# MCU.net
KiCad netlist of a schematic drawn in Altium Designer
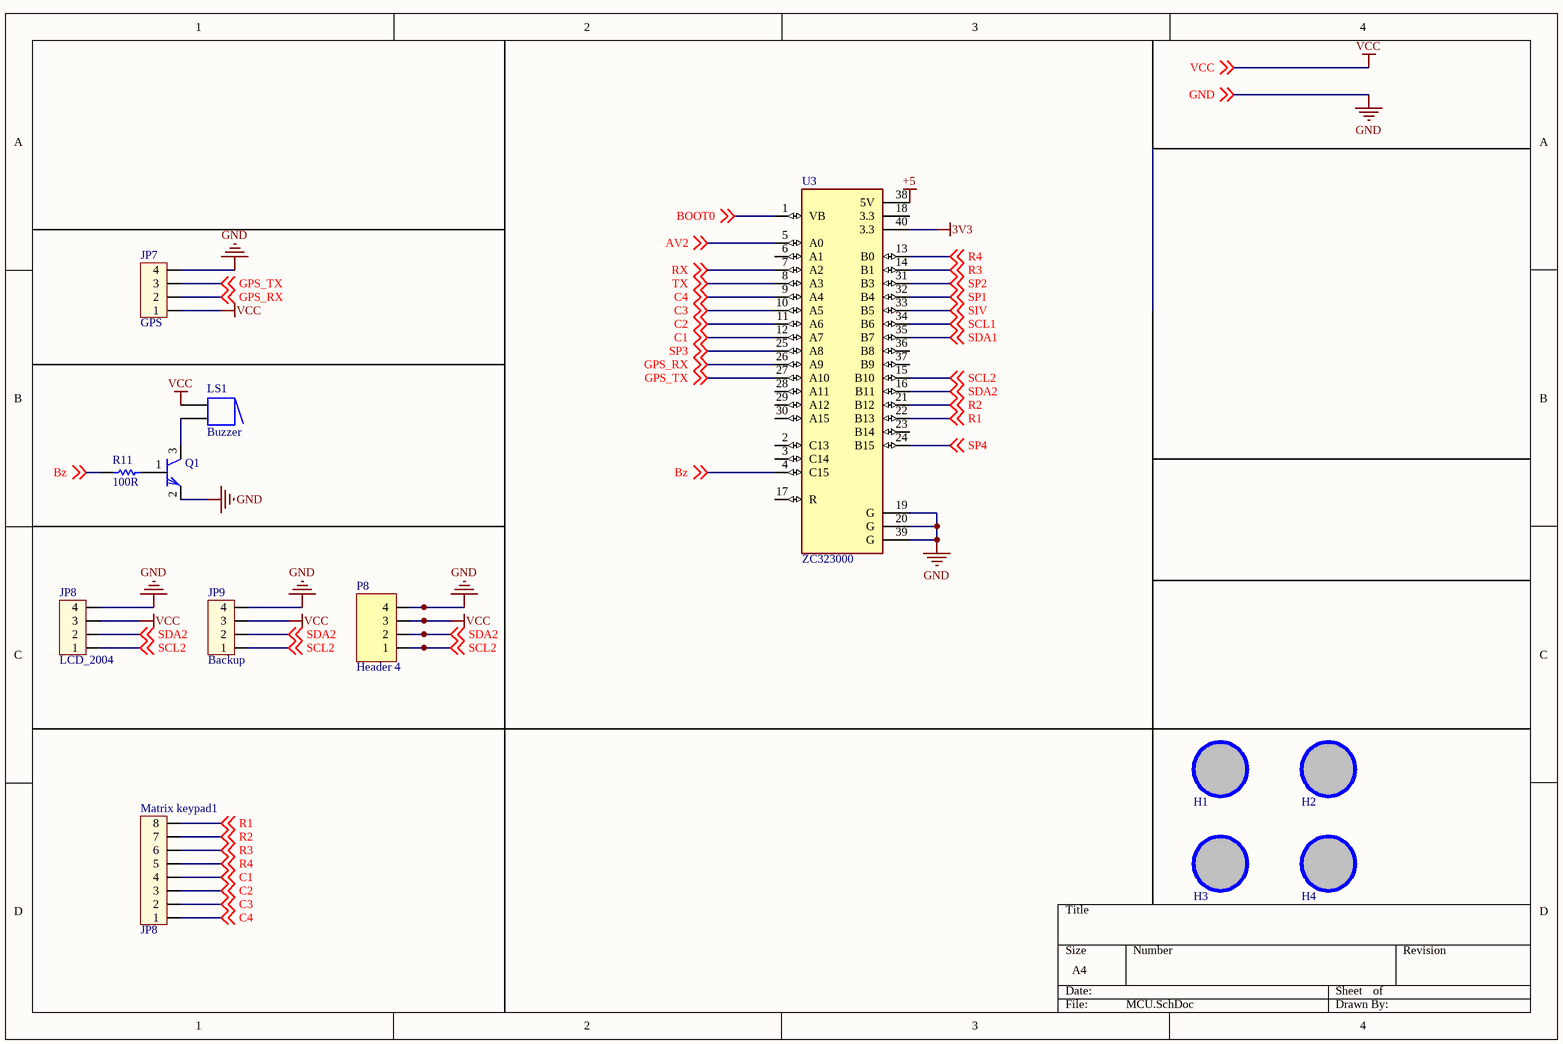
[diagram p0: MCU.SchDoc]

(export (version "E")
  (design (tool "Eeschema 10.0.6"))
  (components
    (comp (ref "H1")
      (value "Hole")
      (footprint "LO KHOAN 3MM")
      (description "Hole 3mm")
      (libsource (lib "thuvienhoang") (part "Hole"))
    )
    (comp (ref "H2")
      (value "Hole")
      (footprint "LO KHOAN 3MM")
      (description "Hole 3mm")
      (libsource (lib "thuvienhoang") (part "Hole"))
    )
    (comp (ref "H3")
      (value "Hole")
      (footprint "LO KHOAN 3MM")
      (description "Hole 3mm")
      (libsource (lib "thuvienhoang") (part "Hole"))
    )
    (comp (ref "H4")
      (value "Hole")
      (footprint "LO KHOAN 3MM")
      (description "Hole 3mm")
      (libsource (lib "thuvienhoang") (part "Hole"))
    )
    (comp (ref "JP7")
      (value "GPS")
      (footprint "CON4")
      (description "Connector 4")
      (libsource (lib "Kiet") (part "Con4"))
    )
    (comp (ref "JP8")
      (value "LCD_2004")
      (footprint "CON4")
      (description "Connector 4")
      (libsource (lib "Kiet") (part "Con4"))
    )
    (comp (ref "JP9")
      (value "Backup")
      (footprint "CON4")
      (description "Connector 4")
      (libsource (lib "Kiet") (part "Con4"))
    )
    (comp (ref "LS1")
      (value "Buzzer")
      (footprint "Buzzer")
      (description "Magnetic Transducer Buzzer")
      (fields (field (name "PUBLISHER") "Altium Limited"))
      (libsource (lib "Kiet") (part "Buzzer"))
    )
    (comp (ref "Matrix keypad1")
      (value "JP8")
      (footprint "CON8")
      (description "Connector 8")
      (libsource (lib "Kiet") (part "Con8"))
    )
    (comp (ref "P8")
      (value "Header 4")
      (footprint "Header 4")
      (description "Header, 4-Pin")
      (fields (field (name "PUBLISHER") "Altium Limited"))
      (libsource (lib "Kiet") (part "Header 4"))
    )
    (comp (ref "Q1")
      (value "C1815")
      (footprint "SOT23 [C1815]")
      (description "Q2SC1815")
      (fields (field (name "PUBLISHER") "Hoang Nguyen"))
      (libsource (lib "Kiet") (part "C1815"))
    )
    (comp (ref "R11")
      (value "100R")
      (footprint "R-0805")
      (description "Resistor")
      (fields (field (name "Comment") "RESISTOR") (field (name "PUBLISHER") "Altium Limited"))
      (libsource (lib "Kiet") (part "RESISTOR"))
    )
    (comp (ref "U3")
      (value "ZC323000")
      (footprint "MODULE_ZC323000")
      (description "STM32F103C8T6 ARM STM32 Minimum System Development Board Module For Arduino")
      (libsource (lib "ZC323000") (part "ZC323000"))
    )
  )
  (nets
    (net (code "1") (name "+5") (class "Default")
      (node (ref "U3") (pin "38") (pinfunction "5V_38") (pintype "power_in"))
    )
    (net (code "3") (name "3V3") (class "Default")
      (node (ref "U3") (pin "40") (pinfunction "3.3_40") (pintype "power_in"))
    )
    (net (code "4") (name "AV2") (class "Default")
      (node (ref "U3") (pin "5") (pinfunction "A0_5") (pintype "bidirectional"))
    )
    (net (code "5") (name "BOOT0") (class "Default")
      (node (ref "U3") (pin "1") (pinfunction "VB_1") (pintype "bidirectional"))
    )
    (net (code "6") (name "Bz") (class "Default")
      (node (ref "R11") (pin "1") (pinfunction "1_1") (pintype "passive"))
      (node (ref "U3") (pin "4") (pinfunction "C15_4") (pintype "bidirectional"))
    )
    (net (code "7") (name "C1") (class "Default")
      (node (ref "Matrix keypad1") (pin "4") (pinfunction "4_4") (pintype "passive"))
      (node (ref "U3") (pin "12") (pinfunction "A7_12") (pintype "bidirectional"))
    )
    (net (code "8") (name "C2") (class "Default")
      (node (ref "Matrix keypad1") (pin "3") (pinfunction "3_3") (pintype "passive"))
      (node (ref "U3") (pin "11") (pinfunction "A6_11") (pintype "bidirectional"))
    )
    (net (code "9") (name "C3") (class "Default")
      (node (ref "Matrix keypad1") (pin "2") (pinfunction "2_2") (pintype "passive"))
      (node (ref "U3") (pin "10") (pinfunction "A5_10") (pintype "bidirectional"))
    )
    (net (code "10") (name "C4") (class "Default")
      (node (ref "Matrix keypad1") (pin "1") (pinfunction "1_1") (pintype "passive"))
      (node (ref "U3") (pin "9") (pinfunction "A4_9") (pintype "bidirectional"))
    )
    (net (code "11") (name "GND") (class "Default")
      (node (ref "JP7") (pin "4") (pinfunction "4_4") (pintype "passive"))
      (node (ref "JP8") (pin "4") (pinfunction "4_4") (pintype "passive"))
      (node (ref "JP9") (pin "4") (pinfunction "4_4") (pintype "passive"))
      (node (ref "P8") (pin "4") (pinfunction "4_4") (pintype "passive"))
      (node (ref "Q1") (pin "2") (pinfunction "E_2") (pintype "passive"))
      (node (ref "U3") (pin "19") (pinfunction "G_19") (pintype "power_in"))
      (node (ref "U3") (pin "20") (pinfunction "G_20") (pintype "power_in"))
      (node (ref "U3") (pin "39") (pinfunction "G_39") (pintype "power_in"))
    )
    (net (code "12") (name "GPS_RX") (class "Default")
      (node (ref "JP7") (pin "2") (pinfunction "2_2") (pintype "passive"))
      (node (ref "U3") (pin "26") (pinfunction "A9_26") (pintype "bidirectional"))
    )
    (net (code "13") (name "GPS_TX") (class "Default")
      (node (ref "JP7") (pin "3") (pinfunction "3_3") (pintype "passive"))
      (node (ref "U3") (pin "27") (pinfunction "A10_27") (pintype "bidirectional"))
    )
    (net (code "14") (name "Net-(Q1-B)") (class "Default")
      (node (ref "Q1") (pin "1") (pinfunction "B_1") (pintype "passive"))
      (node (ref "R11") (pin "2") (pinfunction "2_2") (pintype "passive"))
    )
    (net (code "15") (name "Net-(Q1-C)") (class "Default")
      (node (ref "LS1") (pin "2") (pinfunction "2_2") (pintype "passive"))
      (node (ref "Q1") (pin "3") (pinfunction "C_3") (pintype "passive"))
    )
    (net (code "16") (name "R1") (class "Default")
      (node (ref "Matrix keypad1") (pin "8") (pinfunction "8_8") (pintype "passive"))
      (node (ref "U3") (pin "22") (pinfunction "B13_22") (pintype "bidirectional"))
    )
    (net (code "17") (name "R2") (class "Default")
      (node (ref "Matrix keypad1") (pin "7") (pinfunction "7_7") (pintype "passive"))
      (node (ref "U3") (pin "21") (pinfunction "B12_21") (pintype "bidirectional"))
    )
    (net (code "18") (name "R3") (class "Default")
      (node (ref "Matrix keypad1") (pin "6") (pinfunction "6_6") (pintype "passive"))
      (node (ref "U3") (pin "14") (pinfunction "B1_14") (pintype "bidirectional"))
    )
    (net (code "19") (name "R4") (class "Default")
      (node (ref "Matrix keypad1") (pin "5") (pinfunction "5_5") (pintype "passive"))
      (node (ref "U3") (pin "13") (pinfunction "B0_13") (pintype "bidirectional"))
    )
    (net (code "20") (name "RX") (class "Default")
      (node (ref "U3") (pin "7") (pinfunction "A2_7") (pintype "bidirectional"))
    )
    (net (code "21") (name "SCL1") (class "Default")
      (node (ref "U3") (pin "34") (pinfunction "B6_34") (pintype "bidirectional"))
    )
    (net (code "22") (name "SCL2") (class "Default")
      (node (ref "JP8") (pin "1") (pinfunction "1_1") (pintype "passive"))
      (node (ref "JP9") (pin "1") (pinfunction "1_1") (pintype "passive"))
      (node (ref "P8") (pin "1") (pinfunction "1_1") (pintype "passive"))
      (node (ref "U3") (pin "15") (pinfunction "B10_15") (pintype "bidirectional"))
    )
    (net (code "23") (name "SDA1") (class "Default")
      (node (ref "U3") (pin "35") (pinfunction "B7_35") (pintype "bidirectional"))
    )
    (net (code "24") (name "SDA2") (class "Default")
      (node (ref "JP8") (pin "2") (pinfunction "2_2") (pintype "passive"))
      (node (ref "JP9") (pin "2") (pinfunction "2_2") (pintype "passive"))
      (node (ref "P8") (pin "2") (pinfunction "2_2") (pintype "passive"))
      (node (ref "U3") (pin "16") (pinfunction "B11_16") (pintype "bidirectional"))
    )
    (net (code "25") (name "SIV") (class "Default")
      (node (ref "U3") (pin "33") (pinfunction "B5_33") (pintype "bidirectional"))
    )
    (net (code "26") (name "SP1") (class "Default")
      (node (ref "U3") (pin "32") (pinfunction "B4_32") (pintype "bidirectional"))
    )
    (net (code "27") (name "SP2") (class "Default")
      (node (ref "U3") (pin "31") (pinfunction "B3_31") (pintype "bidirectional"))
    )
    (net (code "28") (name "SP3") (class "Default")
      (node (ref "U3") (pin "25") (pinfunction "A8_25") (pintype "bidirectional"))
    )
    (net (code "29") (name "SP4") (class "Default")
      (node (ref "U3") (pin "24") (pinfunction "B15_24") (pintype "bidirectional"))
    )
    (net (code "30") (name "TX") (class "Default")
      (node (ref "U3") (pin "8") (pinfunction "A3_8") (pintype "bidirectional"))
    )
    (net (code "31") (name "VCC") (class "Default")
      (node (ref "JP7") (pin "1") (pinfunction "1_1") (pintype "passive"))
      (node (ref "JP8") (pin "3") (pinfunction "3_3") (pintype "passive"))
      (node (ref "JP9") (pin "3") (pinfunction "3_3") (pintype "passive"))
      (node (ref "LS1") (pin "1") (pinfunction "1_1") (pintype "passive"))
      (node (ref "P8") (pin "3") (pinfunction "3_3") (pintype "passive"))
    )
    (net (code "32") (name "unconnected-(H1-Pad1)") (class "Default")
      (node (ref "H1") (pin "1") (pinfunction "1_1") (pintype "passive"))
    )
    (net (code "33") (name "unconnected-(H2-Pad1)") (class "Default")
      (node (ref "H2") (pin "1") (pinfunction "1_1") (pintype "passive"))
    )
    (net (code "34") (name "unconnected-(H3-Pad1)") (class "Default")
      (node (ref "H3") (pin "1") (pinfunction "1_1") (pintype "passive"))
    )
    (net (code "35") (name "unconnected-(H4-Pad1)") (class "Default")
      (node (ref "H4") (pin "1") (pinfunction "1_1") (pintype "passive"))
    )
    (net (code "36") (name "unconnected-(U3-3.3-Pad18)") (class "Default")
      (node (ref "U3") (pin "18") (pinfunction "3.3_18") (pintype "power_in"))
    )
    (net (code "37") (name "unconnected-(U3-A1-Pad6)") (class "Default")
      (node (ref "U3") (pin "6") (pinfunction "A1_6") (pintype "bidirectional"))
    )
    (net (code "38") (name "unconnected-(U3-A11-Pad28)") (class "Default")
      (node (ref "U3") (pin "28") (pinfunction "A11_28") (pintype "bidirectional"))
    )
    (net (code "39") (name "unconnected-(U3-A12-Pad29)") (class "Default")
      (node (ref "U3") (pin "29") (pinfunction "A12_29") (pintype "bidirectional"))
    )
    (net (code "40") (name "unconnected-(U3-A15-Pad30)") (class "Default")
      (node (ref "U3") (pin "30") (pinfunction "A15_30") (pintype "bidirectional"))
    )
    (net (code "41") (name "unconnected-(U3-B8-Pad36)") (class "Default")
      (node (ref "U3") (pin "36") (pinfunction "B8_36") (pintype "bidirectional"))
    )
    (net (code "42") (name "unconnected-(U3-B9-Pad37)") (class "Default")
      (node (ref "U3") (pin "37") (pinfunction "B9_37") (pintype "bidirectional"))
    )
    (net (code "43") (name "unconnected-(U3-B14-Pad23)") (class "Default")
      (node (ref "U3") (pin "23") (pinfunction "B14_23") (pintype "bidirectional"))
    )
    (net (code "44") (name "unconnected-(U3-C13-Pad2)") (class "Default")
      (node (ref "U3") (pin "2") (pinfunction "C13_2") (pintype "bidirectional"))
    )
    (net (code "45") (name "unconnected-(U3-C14-Pad3)") (class "Default")
      (node (ref "U3") (pin "3") (pinfunction "C14_3") (pintype "bidirectional"))
    )
    (net (code "46") (name "unconnected-(U3-R-Pad17)") (class "Default")
      (node (ref "U3") (pin "17") (pinfunction "R_17") (pintype "bidirectional"))
    )
  )
)
